# jtag-adapter_1_01.net
KiCad netlist of a schematic drawn in EAGLE
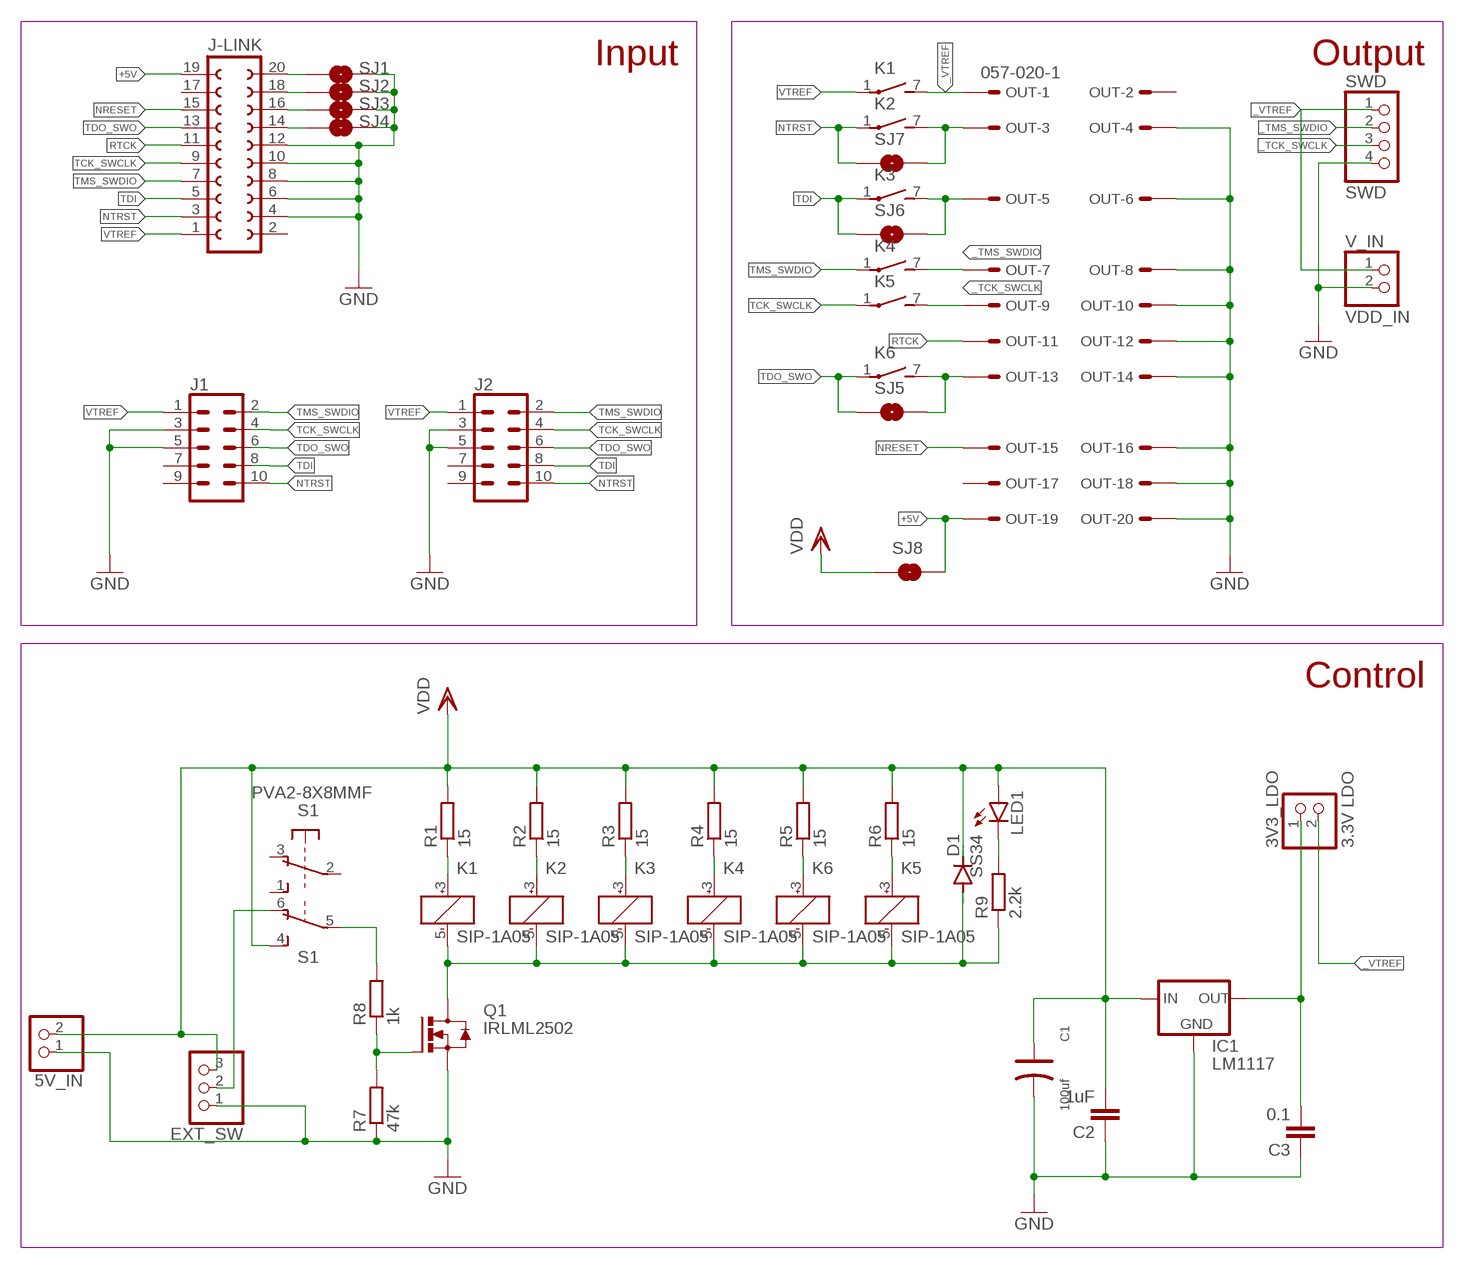
[diagram p0: schematic, sheet 1]

(export (version "E")
  (design (tool "Eeschema 10.0.6"))
  (components
    (comp (ref "3V3_LDO")
      (value "3.3V LDO")
      (footprint "eagle-import:1X02")
      (libsource (lib "eagle-import") (part "PINHD-1X2"))
    )
    (comp (ref "5V_IN")
      (value "PINHD-1X2")
      (footprint "eagle-import:1X02")
      (libsource (lib "eagle-import") (part "PINHD-1X2"))
    )
    (comp (ref "C1")
      (value "100uf")
      (footprint "eagle-import:AVX-B")
      (fields (field (name "MPN") "TAJB476K010RNJ"))
      (libsource (lib "eagle-import") (part "TANTALUM-SMD-47UF-16V-10%(AVX-B)"))
    )
    (comp (ref "C2")
      (value "1uF")
      (footprint "eagle-import:C1206")
      (libsource (lib "eagle-import") (part "C-EUC1206"))
    )
    (comp (ref "C3")
      (value "0.1")
      (footprint "eagle-import:C1206")
      (libsource (lib "eagle-import") (part "C-EUC1206"))
    )
    (comp (ref "D1")
      (value "SS34")
      (footprint "eagle-import:SMB")
      (libsource (lib "eagle-import") (part "DIODE-SMB"))
    )
    (comp (ref "EXT_SW")
      (value "PINHD-1X3")
      (footprint "eagle-import:1X03")
      (libsource (lib "eagle-import") (part "PINHD-1X3"))
    )
    (comp (ref "IC1")
      (value "LM1117")
      (footprint "eagle-import:SOT223")
      (libsource (lib "eagle-import") (part "LM1117"))
    )
    (comp (ref "J-LINK")
      (value "FE10-2W")
      (footprint "eagle-import:FE10-2W")
      (libsource (lib "eagle-import") (part "FE10-2W"))
    )
    (comp (ref "J1")
      (value "CONN_05X20.05_IN_PTH_SILK")
      (footprint "eagle-import:2X5_PTH_SILK_.05")
      (libsource (lib "eagle-import") (part "CONN_05X20.05_IN_PTH_SILK"))
    )
    (comp (ref "J2")
      (value "CONN_05X20.05_IN_PTH_SILK")
      (footprint "eagle-import:2X5_PTH_SILK_.05")
      (libsource (lib "eagle-import") (part "CONN_05X20.05_IN_PTH_SILK"))
    )
    (comp (ref "K1")
      (value "SIP-1A05")
      (footprint "eagle-import:REED")
      (libsource (lib "eagle-import") (part "REED"))
    )
    (comp (ref "K2")
      (value "SIP-1A05")
      (footprint "eagle-import:REED")
      (libsource (lib "eagle-import") (part "REED"))
    )
    (comp (ref "K3")
      (value "SIP-1A05")
      (footprint "eagle-import:REED")
      (libsource (lib "eagle-import") (part "REED"))
    )
    (comp (ref "K4")
      (value "SIP-1A05")
      (footprint "eagle-import:REED")
      (libsource (lib "eagle-import") (part "REED"))
    )
    (comp (ref "K5")
      (value "SIP-1A05")
      (footprint "eagle-import:REED")
      (libsource (lib "eagle-import") (part "REED"))
    )
    (comp (ref "K6")
      (value "SIP-1A05")
      (footprint "eagle-import:REED")
      (libsource (lib "eagle-import") (part "REED"))
    )
    (comp (ref "LED1")
      (value "LEDCHIP-LED0805")
      (footprint "eagle-import:CHIP-LED0805")
      (libsource (lib "eagle-import") (part "LEDCHIP-LED0805"))
    )
    (comp (ref "OUT")
      (value "057-020-1")
      (footprint "eagle-import:057-020-1")
      (libsource (lib "eagle-import") (part "057-020-1"))
    )
    (comp (ref "Q1")
      (value "IRLML2502")
      (footprint "eagle-import:SOT23")
      (libsource (lib "eagle-import") (part "MOSFET_N_SOT231"))
    )
    (comp (ref "R1")
      (value "15")
      (footprint "eagle-import:R0805")
      (libsource (lib "eagle-import") (part "R-EU_R0805"))
    )
    (comp (ref "R2")
      (value "15")
      (footprint "eagle-import:R0805")
      (libsource (lib "eagle-import") (part "R-EU_R0805"))
    )
    (comp (ref "R3")
      (value "15")
      (footprint "eagle-import:R0805")
      (libsource (lib "eagle-import") (part "R-EU_R0805"))
    )
    (comp (ref "R4")
      (value "15")
      (footprint "eagle-import:R0805")
      (libsource (lib "eagle-import") (part "R-EU_R0805"))
    )
    (comp (ref "R5")
      (value "15")
      (footprint "eagle-import:R0805")
      (libsource (lib "eagle-import") (part "R-EU_R0805"))
    )
    (comp (ref "R6")
      (value "15")
      (footprint "eagle-import:R0805")
      (libsource (lib "eagle-import") (part "R-EU_R0805"))
    )
    (comp (ref "R7")
      (value "47k")
      (footprint "eagle-import:R0805")
      (libsource (lib "eagle-import") (part "R-EU_R0805"))
    )
    (comp (ref "R8")
      (value "1k")
      (footprint "eagle-import:R0805")
      (libsource (lib "eagle-import") (part "R-EU_R0805"))
    )
    (comp (ref "R9")
      (value "2.2k")
      (footprint "eagle-import:R0805")
      (libsource (lib "eagle-import") (part "R-EU_R0805"))
    )
    (comp (ref "S1")
      (value "PVA2-8X8MMF")
      (footprint "eagle-import:PVA2F")
      (libsource (lib "eagle-import") (part "PVA2-8X8MMF"))
    )
    (comp (ref "SJ1")
      (value "SOLDERJUMPERTRACE")
      (footprint "eagle-import:SJ_2S-TRACE")
      (libsource (lib "eagle-import") (part "SOLDERJUMPERTRACE"))
    )
    (comp (ref "SJ2")
      (value "SOLDERJUMPERTRACE")
      (footprint "eagle-import:SJ_2S-TRACE")
      (libsource (lib "eagle-import") (part "SOLDERJUMPERTRACE"))
    )
    (comp (ref "SJ3")
      (value "SOLDERJUMPERTRACE")
      (footprint "eagle-import:SJ_2S-TRACE")
      (libsource (lib "eagle-import") (part "SOLDERJUMPERTRACE"))
    )
    (comp (ref "SJ4")
      (value "SOLDERJUMPERTRACE")
      (footprint "eagle-import:SJ_2S-TRACE")
      (libsource (lib "eagle-import") (part "SOLDERJUMPERTRACE"))
    )
    (comp (ref "SJ5")
      (value "SOLDERJUMPERTRACE")
      (footprint "eagle-import:SJ_2S-TRACE")
      (libsource (lib "eagle-import") (part "SOLDERJUMPERTRACE"))
    )
    (comp (ref "SJ6")
      (value "SOLDERJUMPERTRACE")
      (footprint "eagle-import:SJ_2S-TRACE")
      (libsource (lib "eagle-import") (part "SOLDERJUMPERTRACE"))
    )
    (comp (ref "SJ7")
      (value "SOLDERJUMPERTRACE")
      (footprint "eagle-import:SJ_2S-TRACE")
      (libsource (lib "eagle-import") (part "SOLDERJUMPERTRACE"))
    )
    (comp (ref "SJ8")
      (value "SOLDERJUMPERTRACE")
      (footprint "eagle-import:SJ_2S-TRACE")
      (libsource (lib "eagle-import") (part "SOLDERJUMPERTRACE"))
    )
    (comp (ref "SWD")
      (value "SWD")
      (footprint "eagle-import:1X04")
      (libsource (lib "eagle-import") (part "PINHD-1X4"))
    )
    (comp (ref "V_IN")
      (value "VDD_IN")
      (footprint "eagle-import:1X02")
      (libsource (lib "eagle-import") (part "PINHD-1X2"))
    )
  )
  (nets
    (net (code "1") (name "+5V") (class "Default")
      (node (ref "J-LINK") (pin "19") (pinfunction "19_19") (pintype "passive"))
      (node (ref "OUT") (pin "19") (pinfunction "S_19") (pintype "passive"))
      (node (ref "SJ8") (pin "2") (pinfunction "2_2") (pintype "passive"))
    )
    (net (code "2") (name "GND") (class "Default")
      (node (ref "5V_IN") (pin "1") (pinfunction "1_1") (pintype "passive"))
      (node (ref "C1") (pin "-") (pinfunction "-_-") (pintype "passive"))
      (node (ref "C2") (pin "1") (pinfunction "1_1") (pintype "passive"))
      (node (ref "C3") (pin "1") (pinfunction "1_1") (pintype "passive"))
      (node (ref "EXT_SW") (pin "1") (pinfunction "1_1") (pintype "passive"))
      (node (ref "IC1") (pin "1") (pinfunction "GND_1") (pintype "input"))
      (node (ref "J-LINK") (pin "10") (pinfunction "10_10") (pintype "passive"))
      (node (ref "J-LINK") (pin "12") (pinfunction "12_12") (pintype "passive"))
      (node (ref "J-LINK") (pin "4") (pinfunction "4_4") (pintype "passive"))
      (node (ref "J-LINK") (pin "6") (pinfunction "6_6") (pintype "passive"))
      (node (ref "J-LINK") (pin "8") (pinfunction "8_8") (pintype "passive"))
      (node (ref "J1") (pin "3") (pinfunction "3_3") (pintype "passive"))
      (node (ref "J1") (pin "5") (pinfunction "5_5") (pintype "passive"))
      (node (ref "J2") (pin "3") (pinfunction "3_3") (pintype "passive"))
      (node (ref "J2") (pin "5") (pinfunction "5_5") (pintype "passive"))
      (node (ref "OUT") (pin "10") (pinfunction "S_10") (pintype "passive"))
      (node (ref "OUT") (pin "12") (pinfunction "S_12") (pintype "passive"))
      (node (ref "OUT") (pin "14") (pinfunction "S_14") (pintype "passive"))
      (node (ref "OUT") (pin "16") (pinfunction "S_16") (pintype "passive"))
      (node (ref "OUT") (pin "18") (pinfunction "S_18") (pintype "passive"))
      (node (ref "OUT") (pin "20") (pinfunction "S_20") (pintype "passive"))
      (node (ref "OUT") (pin "4") (pinfunction "S_4") (pintype "passive"))
      (node (ref "OUT") (pin "6") (pinfunction "S_6") (pintype "passive"))
      (node (ref "OUT") (pin "8") (pinfunction "S_8") (pintype "passive"))
      (node (ref "Q1") (pin "2") (pinfunction "S_2") (pintype "passive"))
      (node (ref "R7") (pin "1") (pinfunction "1_1") (pintype "passive"))
      (node (ref "SJ1") (pin "2") (pinfunction "2_2") (pintype "passive"))
      (node (ref "SJ2") (pin "2") (pinfunction "2_2") (pintype "passive"))
      (node (ref "SJ3") (pin "2") (pinfunction "2_2") (pintype "passive"))
      (node (ref "SJ4") (pin "2") (pinfunction "2_2") (pintype "passive"))
      (node (ref "SWD") (pin "4") (pinfunction "4_4") (pintype "passive"))
      (node (ref "V_IN") (pin "2") (pinfunction "2_2") (pintype "passive"))
    )
    (net (code "3") (name "NRESET") (class "Default")
      (node (ref "J-LINK") (pin "15") (pinfunction "15_15") (pintype "passive"))
      (node (ref "OUT") (pin "15") (pinfunction "S_15") (pintype "passive"))
    )
    (net (code "4") (name "NTRST") (class "Default")
      (node (ref "J-LINK") (pin "3") (pinfunction "3_3") (pintype "passive"))
      (node (ref "J1") (pin "10") (pinfunction "10_10") (pintype "passive"))
      (node (ref "J2") (pin "10") (pinfunction "10_10") (pintype "passive"))
      (node (ref "K2") (pin "1") (pinfunction "P_1") (pintype "passive"))
      (node (ref "SJ7") (pin "1") (pinfunction "1_1") (pintype "passive"))
    )
    (net (code "5") (name "Net-(IC1-OUT)") (class "Default")
      (node (ref "3V3_LDO") (pin "1") (pinfunction "1_1") (pintype "passive"))
      (node (ref "C3") (pin "2") (pinfunction "2_2") (pintype "passive"))
      (node (ref "IC1") (pin "2") (pinfunction "OUT_2") (pintype "passive"))
    )
    (net (code "6") (name "Net-(J-LINK-Pad14)") (class "Default")
      (node (ref "J-LINK") (pin "14") (pinfunction "14_14") (pintype "passive"))
      (node (ref "SJ4") (pin "1") (pinfunction "1_1") (pintype "passive"))
    )
    (net (code "7") (name "Net-(J-LINK-Pad16)") (class "Default")
      (node (ref "J-LINK") (pin "16") (pinfunction "16_16") (pintype "passive"))
      (node (ref "SJ3") (pin "1") (pinfunction "1_1") (pintype "passive"))
    )
    (net (code "8") (name "Net-(J-LINK-Pad18)") (class "Default")
      (node (ref "J-LINK") (pin "18") (pinfunction "18_18") (pintype "passive"))
      (node (ref "SJ2") (pin "1") (pinfunction "1_1") (pintype "passive"))
    )
    (net (code "9") (name "Net-(J-LINK-Pad20)") (class "Default")
      (node (ref "J-LINK") (pin "20") (pinfunction "20_20") (pintype "passive"))
      (node (ref "SJ1") (pin "1") (pinfunction "1_1") (pintype "passive"))
    )
    (net (code "10") (name "Net-(K1A-+)") (class "Default")
      (node (ref "K1") (pin "3") (pinfunction "+_3") (pintype "passive"))
      (node (ref "R1") (pin "1") (pinfunction "1_1") (pintype "passive"))
    )
    (net (code "11") (name "Net-(K1A--)") (class "Default")
      (node (ref "D1") (pin "A") (pinfunction "A_A") (pintype "passive"))
      (node (ref "K1") (pin "5") (pinfunction "-_5") (pintype "passive"))
      (node (ref "K2") (pin "5") (pinfunction "-_5") (pintype "passive"))
      (node (ref "K3") (pin "5") (pinfunction "-_5") (pintype "passive"))
      (node (ref "K4") (pin "5") (pinfunction "-_5") (pintype "passive"))
      (node (ref "K5") (pin "5") (pinfunction "-_5") (pintype "passive"))
      (node (ref "K6") (pin "5") (pinfunction "-_5") (pintype "passive"))
      (node (ref "Q1") (pin "3") (pinfunction "D_3") (pintype "passive"))
      (node (ref "R9") (pin "1") (pinfunction "1_1") (pintype "passive"))
    )
    (net (code "12") (name "Net-(K2A-+)") (class "Default")
      (node (ref "K2") (pin "3") (pinfunction "+_3") (pintype "passive"))
      (node (ref "R2") (pin "1") (pinfunction "1_1") (pintype "passive"))
    )
    (net (code "13") (name "Net-(K2B-S)") (class "Default")
      (node (ref "K2") (pin "7") (pinfunction "S_7") (pintype "passive"))
      (node (ref "OUT") (pin "3") (pinfunction "S_3") (pintype "passive"))
      (node (ref "SJ7") (pin "2") (pinfunction "2_2") (pintype "passive"))
    )
    (net (code "14") (name "Net-(K3A-+)") (class "Default")
      (node (ref "K3") (pin "3") (pinfunction "+_3") (pintype "passive"))
      (node (ref "R3") (pin "1") (pinfunction "1_1") (pintype "passive"))
    )
    (net (code "15") (name "Net-(K3B-S)") (class "Default")
      (node (ref "K3") (pin "7") (pinfunction "S_7") (pintype "passive"))
      (node (ref "OUT") (pin "5") (pinfunction "S_5") (pintype "passive"))
      (node (ref "SJ6") (pin "2") (pinfunction "2_2") (pintype "passive"))
    )
    (net (code "16") (name "Net-(K4A-+)") (class "Default")
      (node (ref "K4") (pin "3") (pinfunction "+_3") (pintype "passive"))
      (node (ref "R4") (pin "1") (pinfunction "1_1") (pintype "passive"))
    )
    (net (code "17") (name "Net-(K5A-+)") (class "Default")
      (node (ref "K5") (pin "3") (pinfunction "+_3") (pintype "passive"))
      (node (ref "R6") (pin "1") (pinfunction "1_1") (pintype "passive"))
    )
    (net (code "18") (name "Net-(K6A-+)") (class "Default")
      (node (ref "K6") (pin "3") (pinfunction "+_3") (pintype "passive"))
      (node (ref "R5") (pin "1") (pinfunction "1_1") (pintype "passive"))
    )
    (net (code "19") (name "Net-(K6B-S)") (class "Default")
      (node (ref "K6") (pin "7") (pinfunction "S_7") (pintype "passive"))
      (node (ref "OUT") (pin "13") (pinfunction "S_13") (pintype "passive"))
      (node (ref "SJ5") (pin "2") (pinfunction "2_2") (pintype "passive"))
    )
    (net (code "20") (name "Net-(LED1-PadC)") (class "Default")
      (node (ref "LED1") (pin "C") (pinfunction "C_C") (pintype "passive"))
      (node (ref "R9") (pin "2") (pinfunction "2_2") (pintype "passive"))
    )
    (net (code "21") (name "Net-(Q1-G)") (class "Default")
      (node (ref "Q1") (pin "1") (pinfunction "G_1") (pintype "passive"))
      (node (ref "R7") (pin "2") (pinfunction "2_2") (pintype "passive"))
      (node (ref "R8") (pin "1") (pinfunction "1_1") (pintype "passive"))
    )
    (net (code "22") (name "Net-(S1B-O)") (class "Default")
      (node (ref "EXT_SW") (pin "2") (pinfunction "2_2") (pintype "passive"))
      (node (ref "S1") (pin "6") (pinfunction "O_6") (pintype "passive"))
    )
    (net (code "23") (name "Net-(S1B-P)") (class "Default")
      (node (ref "R8") (pin "2") (pinfunction "2_2") (pintype "passive"))
      (node (ref "S1") (pin "5") (pinfunction "P_5") (pintype "passive"))
    )
    (net (code "24") (name "RTCK") (class "Default")
      (node (ref "J-LINK") (pin "11") (pinfunction "11_11") (pintype "passive"))
      (node (ref "OUT") (pin "11") (pinfunction "S_11") (pintype "passive"))
    )
    (net (code "25") (name "TCK_SWCLK") (class "Default")
      (node (ref "J-LINK") (pin "9") (pinfunction "9_9") (pintype "passive"))
      (node (ref "J1") (pin "4") (pinfunction "4_4") (pintype "passive"))
      (node (ref "J2") (pin "4") (pinfunction "4_4") (pintype "passive"))
      (node (ref "K5") (pin "1") (pinfunction "P_1") (pintype "passive"))
    )
    (net (code "26") (name "TDI") (class "Default")
      (node (ref "J-LINK") (pin "5") (pinfunction "5_5") (pintype "passive"))
      (node (ref "J1") (pin "8") (pinfunction "8_8") (pintype "passive"))
      (node (ref "J2") (pin "8") (pinfunction "8_8") (pintype "passive"))
      (node (ref "K3") (pin "1") (pinfunction "P_1") (pintype "passive"))
      (node (ref "SJ6") (pin "1") (pinfunction "1_1") (pintype "passive"))
    )
    (net (code "27") (name "TDO_SWO") (class "Default")
      (node (ref "J-LINK") (pin "13") (pinfunction "13_13") (pintype "passive"))
      (node (ref "J1") (pin "6") (pinfunction "6_6") (pintype "passive"))
      (node (ref "J2") (pin "6") (pinfunction "6_6") (pintype "passive"))
      (node (ref "K6") (pin "1") (pinfunction "P_1") (pintype "passive"))
      (node (ref "SJ5") (pin "1") (pinfunction "1_1") (pintype "passive"))
    )
    (net (code "28") (name "TMS_SWDIO") (class "Default")
      (node (ref "J-LINK") (pin "7") (pinfunction "7_7") (pintype "passive"))
      (node (ref "J1") (pin "2") (pinfunction "2_2") (pintype "passive"))
      (node (ref "J2") (pin "2") (pinfunction "2_2") (pintype "passive"))
      (node (ref "K4") (pin "1") (pinfunction "P_1") (pintype "passive"))
    )
    (net (code "29") (name "VDD") (class "Default")
      (node (ref "5V_IN") (pin "2") (pinfunction "2_2") (pintype "passive"))
      (node (ref "C1") (pin "+") (pinfunction "+_+") (pintype "passive"))
      (node (ref "C2") (pin "2") (pinfunction "2_2") (pintype "passive"))
      (node (ref "D1") (pin "C") (pinfunction "C_C") (pintype "passive"))
      (node (ref "EXT_SW") (pin "3") (pinfunction "3_3") (pintype "passive"))
      (node (ref "IC1") (pin "3") (pinfunction "IN_3") (pintype "input"))
      (node (ref "LED1") (pin "A") (pinfunction "A_A") (pintype "passive"))
      (node (ref "R1") (pin "2") (pinfunction "2_2") (pintype "passive"))
      (node (ref "R2") (pin "2") (pinfunction "2_2") (pintype "passive"))
      (node (ref "R3") (pin "2") (pinfunction "2_2") (pintype "passive"))
      (node (ref "R4") (pin "2") (pinfunction "2_2") (pintype "passive"))
      (node (ref "R5") (pin "2") (pinfunction "2_2") (pintype "passive"))
      (node (ref "R6") (pin "2") (pinfunction "2_2") (pintype "passive"))
      (node (ref "S1") (pin "4") (pinfunction "S_4") (pintype "passive"))
      (node (ref "SJ8") (pin "1") (pinfunction "1_1") (pintype "passive"))
    )
    (net (code "30") (name "VTREF") (class "Default")
      (node (ref "J-LINK") (pin "1") (pinfunction "1_1") (pintype "passive"))
      (node (ref "J1") (pin "1") (pinfunction "1_1") (pintype "passive"))
      (node (ref "J2") (pin "1") (pinfunction "1_1") (pintype "passive"))
      (node (ref "K1") (pin "1") (pinfunction "P_1") (pintype "passive"))
    )
    (net (code "31") (name "_TCK_SWCLK") (class "Default")
      (node (ref "K5") (pin "7") (pinfunction "S_7") (pintype "passive"))
      (node (ref "OUT") (pin "9") (pinfunction "S_9") (pintype "passive"))
      (node (ref "SWD") (pin "3") (pinfunction "3_3") (pintype "passive"))
    )
    (net (code "32") (name "_TMS_SWDIO") (class "Default")
      (node (ref "K4") (pin "7") (pinfunction "S_7") (pintype "passive"))
      (node (ref "OUT") (pin "7") (pinfunction "S_7") (pintype "passive"))
      (node (ref "SWD") (pin "2") (pinfunction "2_2") (pintype "passive"))
    )
    (net (code "33") (name "_VTREF") (class "Default")
      (node (ref "3V3_LDO") (pin "2") (pinfunction "2_2") (pintype "passive"))
      (node (ref "K1") (pin "7") (pinfunction "S_7") (pintype "passive"))
      (node (ref "OUT") (pin "1") (pinfunction "S_1") (pintype "passive"))
      (node (ref "SWD") (pin "1") (pinfunction "1_1") (pintype "passive"))
      (node (ref "V_IN") (pin "1") (pinfunction "1_1") (pintype "passive"))
    )
    (net (code "34") (name "unconnected-(J-LINK-Pad2)") (class "Default")
      (node (ref "J-LINK") (pin "2") (pinfunction "2_2") (pintype "passive"))
    )
    (net (code "35") (name "unconnected-(J-LINK-Pad17)") (class "Default")
      (node (ref "J-LINK") (pin "17") (pinfunction "17_17") (pintype "passive"))
    )
    (net (code "36") (name "unconnected-(J1-Pad7)") (class "Default")
      (node (ref "J1") (pin "7") (pinfunction "7_7") (pintype "passive"))
    )
    (net (code "37") (name "unconnected-(J1-Pad9)") (class "Default")
      (node (ref "J1") (pin "9") (pinfunction "9_9") (pintype "passive"))
    )
    (net (code "38") (name "unconnected-(J2-Pad7)") (class "Default")
      (node (ref "J2") (pin "7") (pinfunction "7_7") (pintype "passive"))
    )
    (net (code "39") (name "unconnected-(J2-Pad9)") (class "Default")
      (node (ref "J2") (pin "9") (pinfunction "9_9") (pintype "passive"))
    )
    (net (code "40") (name "unconnected-(OUTI-S-Pad17)") (class "Default")
      (node (ref "OUT") (pin "17") (pinfunction "S_17") (pintype "passive"))
    )
    (net (code "41") (name "unconnected-(OUTL-S-Pad2)") (class "Default")
      (node (ref "OUT") (pin "2") (pinfunction "S_2") (pintype "passive"))
    )
    (net (code "42") (name "unconnected-(S1A-O-Pad3)") (class "Default")
      (node (ref "S1") (pin "3") (pinfunction "O_3") (pintype "passive"))
    )
    (net (code "43") (name "unconnected-(S1A-P-Pad2)") (class "Default")
      (node (ref "S1") (pin "2") (pinfunction "P_2") (pintype "passive"))
    )
    (net (code "44") (name "unconnected-(S1A-S-Pad1)") (class "Default")
      (node (ref "S1") (pin "1") (pinfunction "S_1") (pintype "passive"))
    )
  )
)
